# 5_to_var.net
KiCad netlist of a schematic drawn in EAGLE
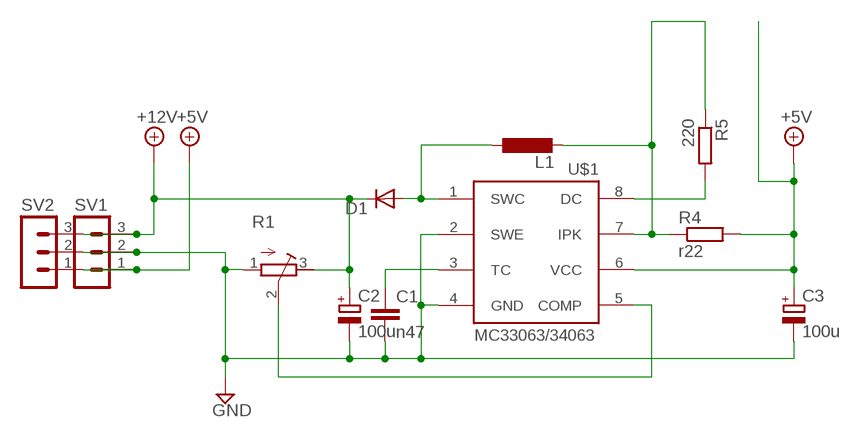
[diagram p0: schematic, sheet 1]

(export (version "E")
  (design (tool "Eeschema 10.0.6"))
  (components
    (comp (ref "C1")
      (value "n47")
      (footprint "eagle-import:C025-025X050")
      (libsource (lib "eagle-import") (part "C-EU025-025X050"))
    )
    (comp (ref "C2")
      (value "100u")
      (footprint "eagle-import:E2,5-7")
      (libsource (lib "eagle-import") (part "CPOL-EUE2.5-7"))
    )
    (comp (ref "C3")
      (value "100u")
      (footprint "eagle-import:E2,5-7")
      (libsource (lib "eagle-import") (part "CPOL-EUE2.5-7"))
    )
    (comp (ref "D1")
      (value "DIODE-D-2.5")
      (footprint "eagle-import:D-2.5")
      (libsource (lib "eagle-import") (part "DIODE-D-2.5"))
    )
    (comp (ref "L1")
      (value "L-EU0207/2V")
      (footprint "eagle-import:0207_2V")
      (libsource (lib "eagle-import") (part "L-EU0207/2V"))
    )
    (comp (ref "R1")
      (value "R-TRIMM3296X")
      (footprint "eagle-import:RTRIM3296X")
      (libsource (lib "eagle-import") (part "R-TRIMM3296X"))
    )
    (comp (ref "R4")
      (value "r22")
      (footprint "eagle-import:0207_2V")
      (libsource (lib "eagle-import") (part "R-EU_0207/2V"))
    )
    (comp (ref "R5")
      (value "220")
      (footprint "eagle-import:0207_2V")
      (libsource (lib "eagle-import") (part "R-EU_0207/2V"))
    )
    (comp (ref "SV1")
      (value "MA03-1")
      (footprint "eagle-import:MA03-1")
      (libsource (lib "eagle-import") (part "MA03-1"))
    )
    (comp (ref "SV2")
      (value "MA03-1")
      (footprint "eagle-import:MA03-1")
      (libsource (lib "eagle-import") (part "MA03-1"))
    )
    (comp (ref "U$1")
      (value "MC33063/MC34063P")
      (footprint "eagle-import:DIL08")
      (libsource (lib "eagle-import") (part "MC33063/MC34063P"))
    )
  )
  (nets
    (net (code "1") (name "+5V") (class "Default")
      (node (ref "C3") (pin "+") (pinfunction "+_+") (pintype "passive"))
      (node (ref "R4") (pin "2") (pinfunction "2_2") (pintype "passive"))
      (node (ref "SV1") (pin "1") (pinfunction "1_1") (pintype "passive"))
      (node (ref "SV2") (pin "1") (pinfunction "1_1") (pintype "passive"))
      (node (ref "U$1") (pin "6") (pinfunction "VCC_6") (pintype "power_in"))
    )
    (net (code "2") (name "+12V") (class "Default")
      (node (ref "C2") (pin "+") (pinfunction "+_+") (pintype "passive"))
      (node (ref "D1") (pin "C") (pinfunction "C_C") (pintype "passive"))
      (node (ref "R1") (pin "3") (pinfunction "E_3") (pintype "passive"))
      (node (ref "SV1") (pin "3") (pinfunction "3_3") (pintype "passive"))
      (node (ref "SV2") (pin "3") (pinfunction "3_3") (pintype "passive"))
    )
    (net (code "3") (name "GND") (class "Default")
      (node (ref "C1") (pin "2") (pinfunction "2_2") (pintype "passive"))
      (node (ref "C2") (pin "-") (pinfunction "-_-") (pintype "passive"))
      (node (ref "C3") (pin "-") (pinfunction "-_-") (pintype "passive"))
      (node (ref "R1") (pin "1") (pinfunction "A_1") (pintype "passive"))
      (node (ref "SV1") (pin "2") (pinfunction "2_2") (pintype "passive"))
      (node (ref "SV2") (pin "2") (pinfunction "2_2") (pintype "passive"))
      (node (ref "U$1") (pin "2") (pinfunction "SWE_2") (pintype "input"))
      (node (ref "U$1") (pin "4") (pinfunction "GND_4") (pintype "power_in"))
    )
    (net (code "4") (name "Net-(R1-S)") (class "Default")
      (node (ref "R1") (pin "2") (pinfunction "S_2") (pintype "passive"))
      (node (ref "U$1") (pin "5") (pinfunction "COMP_5") (pintype "input"))
    )
    (net (code "5") (name "Net-(U$1-DC)") (class "Default")
      (node (ref "R5") (pin "2") (pinfunction "2_2") (pintype "passive"))
      (node (ref "U$1") (pin "8") (pinfunction "DC_8") (pintype "input"))
    )
    (net (code "6") (name "Net-(U$1-IPK)") (class "Default")
      (node (ref "L1") (pin "2") (pinfunction "2_2") (pintype "passive"))
      (node (ref "R4") (pin "1") (pinfunction "1_1") (pintype "passive"))
      (node (ref "R5") (pin "1") (pinfunction "1_1") (pintype "passive"))
      (node (ref "U$1") (pin "7") (pinfunction "IPK_7") (pintype "bidirectional"))
    )
    (net (code "7") (name "Net-(U$1-SWC)") (class "Default")
      (node (ref "D1") (pin "A") (pinfunction "A_A") (pintype "passive"))
      (node (ref "L1") (pin "1") (pinfunction "1_1") (pintype "passive"))
      (node (ref "U$1") (pin "1") (pinfunction "SWC_1") (pintype "input"))
    )
    (net (code "8") (name "Net-(U$1-TC)") (class "Default")
      (node (ref "C1") (pin "1") (pinfunction "1_1") (pintype "passive"))
      (node (ref "U$1") (pin "3") (pinfunction "TC_3") (pintype "input"))
    )
  )
)
